# MINI_SAM_2017-01-001.net
KiCad netlist of a schematic drawn in EAGLE
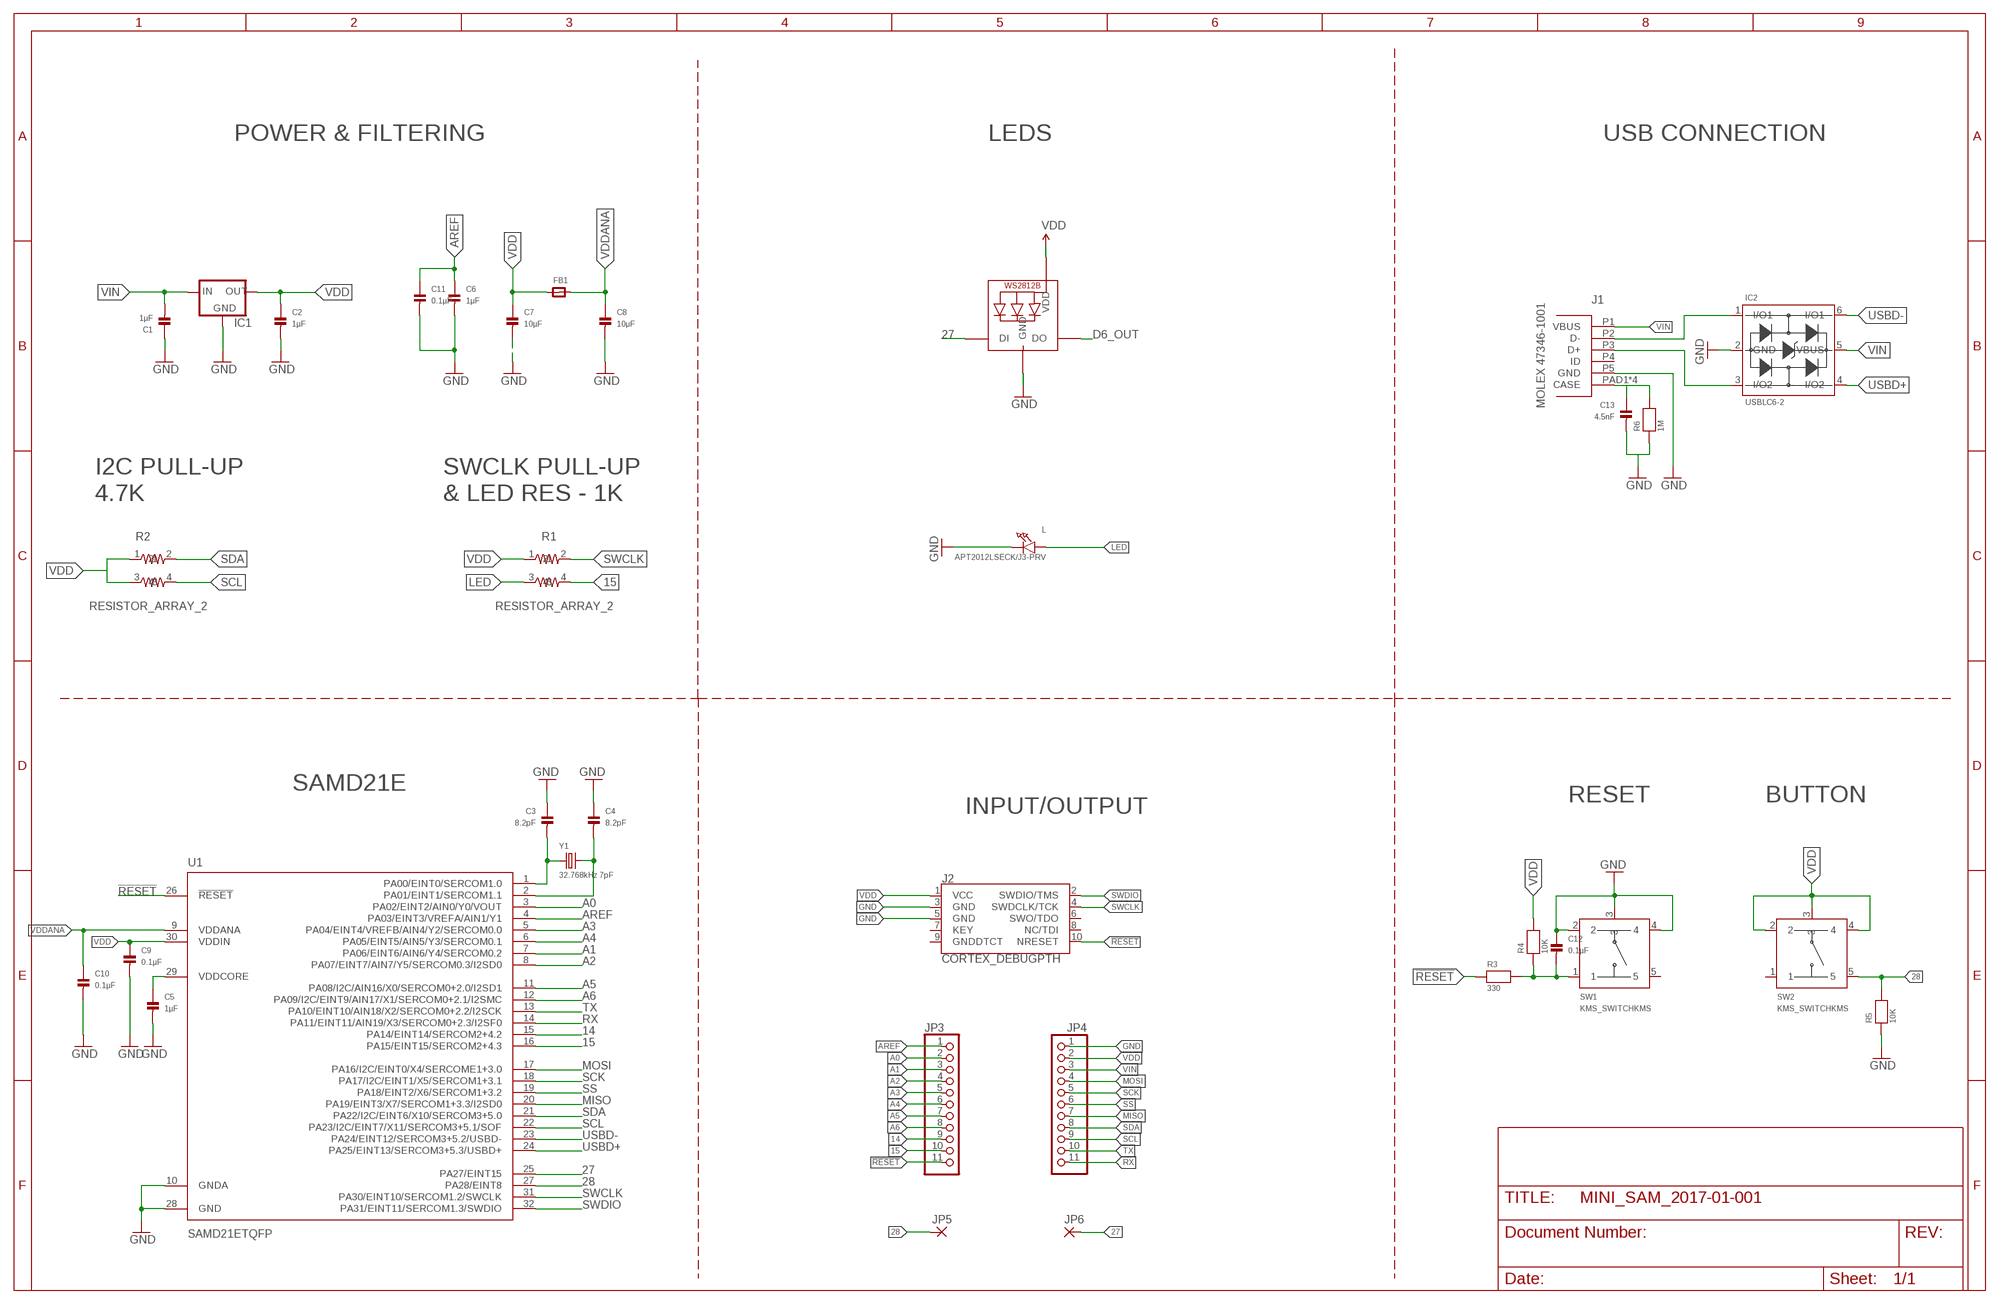
[diagram p0: schematic, sheet 1]

(export (version "E")
  (design (tool "Eeschema 10.0.6"))
  (components
    (comp (ref "C1")
      (value "1µF")
      (footprint "eagle-import:_0805MP")
      (libsource (lib "eagle-import") (part "CAP_CERAMIC_0805MP"))
    )
    (comp (ref "C2")
      (value "1µF")
      (footprint "eagle-import:_0805MP")
      (libsource (lib "eagle-import") (part "CAP_CERAMIC_0805MP"))
    )
    (comp (ref "C3")
      (value "8.2pF")
      (footprint "eagle-import:_0805MP")
      (libsource (lib "eagle-import") (part "CAP_CERAMIC_0805MP"))
    )
    (comp (ref "C4")
      (value "8.2pF")
      (footprint "eagle-import:_0805MP")
      (libsource (lib "eagle-import") (part "CAP_CERAMIC_0805MP"))
    )
    (comp (ref "C5")
      (value "1µF")
      (footprint "eagle-import:_0805MP")
      (libsource (lib "eagle-import") (part "CAP_CERAMIC_0805MP"))
    )
    (comp (ref "C6")
      (value "1µF")
      (footprint "eagle-import:_0805MP")
      (libsource (lib "eagle-import") (part "CAP_CERAMIC_0805MP"))
    )
    (comp (ref "C7")
      (value "10µF")
      (footprint "eagle-import:_0805MP")
      (libsource (lib "eagle-import") (part "CAP_CERAMIC_0805MP"))
    )
    (comp (ref "C8")
      (value "10µF")
      (footprint "eagle-import:_0805MP")
      (libsource (lib "eagle-import") (part "CAP_CERAMIC_0805MP"))
    )
    (comp (ref "C9")
      (value "0.1µF")
      (footprint "eagle-import:_0805MP")
      (libsource (lib "eagle-import") (part "CAP_CERAMIC_0805MP"))
    )
    (comp (ref "C10")
      (value "0.1µF")
      (footprint "eagle-import:_0805MP")
      (libsource (lib "eagle-import") (part "CAP_CERAMIC_0805MP"))
    )
    (comp (ref "C11")
      (value "0.1µF")
      (footprint "eagle-import:_0805MP")
      (libsource (lib "eagle-import") (part "CAP_CERAMIC_0805MP"))
    )
    (comp (ref "C12")
      (value "0.1µF")
      (footprint "eagle-import:_0805MP")
      (libsource (lib "eagle-import") (part "CAP_CERAMIC_0805MP"))
    )
    (comp (ref "C13")
      (value "4.5nF")
      (footprint "eagle-import:_0805MP")
      (libsource (lib "eagle-import") (part "CAP_CERAMIC_0805MP"))
    )
    (comp (ref "FB1")
      (value "FERRITE_0805MP")
      (footprint "eagle-import:_0805MP")
      (libsource (lib "eagle-import") (part "FERRITE_0805MP"))
    )
    (comp (ref "IC1")
      (value "MCP1700")
      (footprint "eagle-import:SOT23")
      (libsource (lib "eagle-import") (part "MCP1700"))
    )
    (comp (ref "IC2")
      (value "USBLC6-2")
      (footprint "eagle-import:SOT23-6L")
      (libsource (lib "eagle-import") (part "USBLC6-2"))
    )
    (comp (ref "J1")
      (value "MOLEX_47346-100147346")
      (footprint "eagle-import:MOLEX_47346-1001")
      (libsource (lib "eagle-import") (part "MOLEX_47346-100147346"))
    )
    (comp (ref "J2")
      (value "CORTEX_DEBUGPTH")
      (footprint "eagle-import:2X5-PTH-1.27MM")
      (libsource (lib "eagle-import") (part "CORTEX_DEBUGPTH"))
    )
    (comp (ref "JP3")
      (value "PINHD-1X111X11_SMT")
      (footprint "eagle-import:1X11_SMT")
      (libsource (lib "eagle-import") (part "PINHD-1X111X11_SMT"))
    )
    (comp (ref "JP4")
      (value "PINHD-1X111X11_SMT")
      (footprint "eagle-import:1X11_SMT")
      (libsource (lib "eagle-import") (part "PINHD-1X111X11_SMT"))
    )
    (comp (ref "JP5")
      (value "FR11_PAD2MMX1MM")
      (footprint "eagle-import:SMD2MMX1MM")
      (libsource (lib "eagle-import") (part "FR11_PAD2MMX1MM"))
    )
    (comp (ref "JP6")
      (value "FR11_PAD2MMX1MM")
      (footprint "eagle-import:SMD2MMX1MM")
      (libsource (lib "eagle-import") (part "FR11_PAD2MMX1MM"))
    )
    (comp (ref "L")
      (value "APT2012LSECK/J3-PRV")
      (footprint "eagle-import:CHIPLED_0603_NOOUTLINE")
      (libsource (lib "eagle-import") (part "LED0603_NOOUTLINE"))
    )
    (comp (ref "R1")
      (value "RESISTOR_ARRAY_2")
      (footprint "eagle-import:RESISTOR_ARRAY_0606")
      (libsource (lib "eagle-import") (part "RESISTOR_ARRAY_2"))
    )
    (comp (ref "R2")
      (value "RESISTOR_ARRAY_2")
      (footprint "eagle-import:RESISTOR_ARRAY_0606")
      (libsource (lib "eagle-import") (part "RESISTOR_ARRAY_2"))
    )
    (comp (ref "R3")
      (value "330")
      (footprint "eagle-import:_0805MP")
      (libsource (lib "eagle-import") (part "RESISTOR_0805MP"))
    )
    (comp (ref "R4")
      (value "10K")
      (footprint "eagle-import:_0805MP")
      (libsource (lib "eagle-import") (part "RESISTOR_0805MP"))
    )
    (comp (ref "R5")
      (value "10K")
      (footprint "eagle-import:_0805MP")
      (libsource (lib "eagle-import") (part "RESISTOR_0805MP"))
    )
    (comp (ref "R6")
      (value "1M")
      (footprint "eagle-import:_0805MP")
      (libsource (lib "eagle-import") (part "RESISTOR_0805MP"))
    )
    (comp (ref "STATUS")
      (value "WS2812B3535")
      (footprint "eagle-import:LED3535")
      (libsource (lib "eagle-import") (part "WS2812B3535"))
    )
    (comp (ref "SW1")
      (value "KMS_SWITCHKMS")
      (footprint "eagle-import:KMS_SWITCH")
      (libsource (lib "eagle-import") (part "KMS_SWITCHKMS"))
    )
    (comp (ref "SW2")
      (value "KMS_SWITCHKMS")
      (footprint "eagle-import:KMS_SWITCH")
      (libsource (lib "eagle-import") (part "KMS_SWITCHKMS"))
    )
    (comp (ref "U1")
      (value "SAMD21ETQFP")
      (footprint "eagle-import:TQFP32-08")
      (libsource (lib "eagle-import") (part "SAMD21ETQFP"))
    )
    (comp (ref "Y1")
      (value "32.768kHz 7pF")
      (footprint "eagle-import:_0805MP")
      (libsource (lib "eagle-import") (part "CRYSTAL0805PACKAGE"))
    )
  )
  (nets
    (net (code "1") (name "/D6_OUT") (class "Default")
      (node (ref "STATUS") (pin "3") (pinfunction "DO_3") (pintype "output"))
    )
    (net (code "2") (name "/~{RESET}") (class "Default")
      (node (ref "J2") (pin "10") (pinfunction "NRESET_10") (pintype "bidirectional"))
      (node (ref "JP3") (pin "11") (pinfunction "11_11") (pintype "passive"))
      (node (ref "R3") (pin "1") (pinfunction "1_1") (pintype "passive"))
      (node (ref "U1") (pin "26") (pinfunction "~{RESET}_26") (pintype "bidirectional"))
    )
    (net (code "3") (name "14") (class "Default")
      (node (ref "JP3") (pin "9") (pinfunction "9_9") (pintype "passive"))
      (node (ref "U1") (pin "15") (pinfunction "PA14/EINT14/SERCOM2+4.2_15") (pintype "bidirectional"))
    )
    (net (code "4") (name "15") (class "Default")
      (node (ref "JP3") (pin "10") (pinfunction "10_10") (pintype "passive"))
      (node (ref "R1") (pin "4") (pinfunction "4_4") (pintype "passive"))
      (node (ref "U1") (pin "16") (pinfunction "PA15/EINT15/SERCOM2+4.3_16") (pintype "bidirectional"))
    )
    (net (code "5") (name "27") (class "Default")
      (node (ref "JP6") (pin "P$1") (pinfunction "P_P$1") (pintype "passive"))
      (node (ref "STATUS") (pin "1") (pinfunction "DI_1") (pintype "input"))
      (node (ref "U1") (pin "25") (pinfunction "PA27/EINT15_25") (pintype "bidirectional"))
    )
    (net (code "6") (name "28") (class "Default")
      (node (ref "JP5") (pin "P$1") (pinfunction "P_P$1") (pintype "passive"))
      (node (ref "R5") (pin "2") (pinfunction "2_2") (pintype "passive"))
      (node (ref "SW2") (pin "5") (pinfunction "5_5") (pintype "bidirectional"))
      (node (ref "U1") (pin "27") (pinfunction "PA28/EINT8_27") (pintype "bidirectional"))
    )
    (net (code "7") (name "A0") (class "Default")
      (node (ref "JP3") (pin "2") (pinfunction "2_2") (pintype "passive"))
      (node (ref "U1") (pin "3") (pinfunction "PA02/EINT2/AIN0/Y0/VOUT_3") (pintype "bidirectional"))
    )
    (net (code "8") (name "A1") (class "Default")
      (node (ref "JP3") (pin "3") (pinfunction "3_3") (pintype "passive"))
      (node (ref "U1") (pin "7") (pinfunction "PA06/EINT6/AIN6/Y4/SERCOM0.2_7") (pintype "bidirectional"))
    )
    (net (code "9") (name "A2") (class "Default")
      (node (ref "JP3") (pin "4") (pinfunction "4_4") (pintype "passive"))
      (node (ref "U1") (pin "8") (pinfunction "PA07/EINT7/AIN7/Y5/SERCOM0.3/I2SD0_8") (pintype "bidirectional"))
    )
    (net (code "10") (name "A3") (class "Default")
      (node (ref "JP3") (pin "5") (pinfunction "5_5") (pintype "passive"))
      (node (ref "U1") (pin "5") (pinfunction "PA04/EINT4/VREFB/AIN4/Y2/SERCOM0.0_5") (pintype "bidirectional"))
    )
    (net (code "11") (name "A4") (class "Default")
      (node (ref "JP3") (pin "6") (pinfunction "6_6") (pintype "passive"))
      (node (ref "U1") (pin "6") (pinfunction "PA05/EINT5/AIN5/Y3/SERCOM0.1_6") (pintype "bidirectional"))
    )
    (net (code "12") (name "A5") (class "Default")
      (node (ref "JP3") (pin "7") (pinfunction "7_7") (pintype "passive"))
      (node (ref "U1") (pin "11") (pinfunction "PA08/I2C/AIN16/X0/SERCOM0+2.0/I2SD1_11") (pintype "bidirectional"))
    )
    (net (code "13") (name "A6") (class "Default")
      (node (ref "JP3") (pin "8") (pinfunction "8_8") (pintype "passive"))
      (node (ref "U1") (pin "12") (pinfunction "PA09/I2C/EINT9/AIN17/X1/SERCOM0+2.1/I2SMC_12") (pintype "bidirectional"))
    )
    (net (code "14") (name "AREF") (class "Default")
      (node (ref "C11") (pin "1") (pinfunction "P$1_1") (pintype "passive"))
      (node (ref "C6") (pin "1") (pinfunction "P$1_1") (pintype "passive"))
      (node (ref "JP3") (pin "1") (pinfunction "1_1") (pintype "passive"))
      (node (ref "U1") (pin "4") (pinfunction "PA03/EINT3/VREFA/AIN1/Y1_4") (pintype "bidirectional"))
    )
    (net (code "15") (name "GND") (class "Default")
      (node (ref "C1") (pin "1") (pinfunction "P$1_1") (pintype "passive"))
      (node (ref "C10") (pin "2") (pinfunction "P$2_2") (pintype "passive"))
      (node (ref "C11") (pin "2") (pinfunction "P$2_2") (pintype "passive"))
      (node (ref "C12") (pin "1") (pinfunction "P$1_1") (pintype "passive"))
      (node (ref "C13") (pin "2") (pinfunction "P$2_2") (pintype "passive"))
      (node (ref "C2") (pin "2") (pinfunction "P$2_2") (pintype "passive"))
      (node (ref "C3") (pin "1") (pinfunction "P$1_1") (pintype "passive"))
      (node (ref "C4") (pin "1") (pinfunction "P$1_1") (pintype "passive"))
      (node (ref "C5") (pin "2") (pinfunction "P$2_2") (pintype "passive"))
      (node (ref "C6") (pin "2") (pinfunction "P$2_2") (pintype "passive"))
      (node (ref "C7") (pin "2") (pinfunction "P$2_2") (pintype "passive"))
      (node (ref "C8") (pin "2") (pinfunction "P$2_2") (pintype "passive"))
      (node (ref "C9") (pin "2") (pinfunction "P$2_2") (pintype "passive"))
      (node (ref "IC1") (pin "1") (pinfunction "GND_1") (pintype "input"))
      (node (ref "IC2") (pin "2") (pinfunction "GND_2") (pintype "bidirectional"))
      (node (ref "J1") (pin "P5") (pinfunction "GND_P5") (pintype "power_in"))
      (node (ref "J2") (pin "3") (pinfunction "GND_3") (pintype "bidirectional"))
      (node (ref "J2") (pin "5") (pinfunction "GND_5") (pintype "bidirectional"))
      (node (ref "JP4") (pin "1") (pinfunction "1_1") (pintype "passive"))
      (node (ref "L") (pin "C") (pinfunction "C_C") (pintype "passive"))
      (node (ref "R5") (pin "1") (pinfunction "1_1") (pintype "passive"))
      (node (ref "R6") (pin "1") (pinfunction "1_1") (pintype "passive"))
      (node (ref "STATUS") (pin "4") (pinfunction "GND_4") (pintype "power_in"))
      (node (ref "SW1") (pin "2") (pinfunction "2_2") (pintype "bidirectional"))
      (node (ref "SW1") (pin "3") (pinfunction "3_3") (pintype "bidirectional"))
      (node (ref "SW1") (pin "4") (pinfunction "4_4") (pintype "bidirectional"))
      (node (ref "U1") (pin "10") (pinfunction "GNDA_10") (pintype "power_in"))
      (node (ref "U1") (pin "28") (pinfunction "GND_28") (pintype "power_in"))
    )
    (net (code "16") (name "LED") (class "Default")
      (node (ref "L") (pin "A") (pinfunction "A_A") (pintype "passive"))
      (node (ref "R1") (pin "3") (pinfunction "3_3") (pintype "passive"))
    )
    (net (code "17") (name "MISO") (class "Default")
      (node (ref "JP4") (pin "7") (pinfunction "7_7") (pintype "passive"))
      (node (ref "U1") (pin "20") (pinfunction "PA19/EINT3/X7/SERCOM1+3.3/I2SD0_20") (pintype "bidirectional"))
    )
    (net (code "18") (name "MOSI") (class "Default")
      (node (ref "JP4") (pin "4") (pinfunction "4_4") (pintype "passive"))
      (node (ref "U1") (pin "17") (pinfunction "PA16/I2C/EINT0/X4/SERCOME1+3.0_17") (pintype "bidirectional"))
    )
    (net (code "19") (name "Net-(C3-P$2)") (class "Default")
      (node (ref "C3") (pin "2") (pinfunction "P$2_2") (pintype "passive"))
      (node (ref "U1") (pin "1") (pinfunction "PA00/EINT0/SERCOM1.0_1") (pintype "bidirectional"))
      (node (ref "Y1") (pin "1") (pinfunction "1_1") (pintype "passive"))
    )
    (net (code "20") (name "Net-(C4-P$2)") (class "Default")
      (node (ref "C4") (pin "2") (pinfunction "P$2_2") (pintype "passive"))
      (node (ref "U1") (pin "2") (pinfunction "PA01/EINT1/SERCOM1.1_2") (pintype "bidirectional"))
      (node (ref "Y1") (pin "2") (pinfunction "2_2") (pintype "passive"))
    )
    (net (code "21") (name "Net-(C5-P$1)") (class "Default")
      (node (ref "C5") (pin "1") (pinfunction "P$1_1") (pintype "passive"))
      (node (ref "U1") (pin "29") (pinfunction "VDDCORE_29") (pintype "power_in"))
    )
    (net (code "22") (name "Net-(C12-P$2)") (class "Default")
      (node (ref "C12") (pin "2") (pinfunction "P$2_2") (pintype "passive"))
      (node (ref "R3") (pin "2") (pinfunction "2_2") (pintype "passive"))
      (node (ref "R4") (pin "1") (pinfunction "1_1") (pintype "passive"))
      (node (ref "SW1") (pin "1") (pinfunction "1_1") (pintype "bidirectional"))
    )
    (net (code "23") (name "Net-(C13-P$1)") (class "Default")
      (node (ref "C13") (pin "1") (pinfunction "P$1_1") (pintype "passive"))
      (node (ref "J1") (pin "PAD1") (pinfunction "CASE_PAD1") (pintype "bidirectional"))
      (node (ref "J1") (pin "PAD2") (pinfunction "CASE_PAD2") (pintype "bidirectional"))
      (node (ref "J1") (pin "PAD3") (pinfunction "CASE_PAD3") (pintype "bidirectional"))
      (node (ref "J1") (pin "PAD4") (pinfunction "CASE_PAD4") (pintype "bidirectional"))
      (node (ref "R6") (pin "2") (pinfunction "2_2") (pintype "passive"))
    )
    (net (code "24") (name "Net-(J1-D+)") (class "Default")
      (node (ref "IC2") (pin "3") (pinfunction "I/O2_3") (pintype "bidirectional"))
      (node (ref "J1") (pin "P3") (pinfunction "D+_P3") (pintype "bidirectional"))
    )
    (net (code "25") (name "Net-(J1-D-)") (class "Default")
      (node (ref "IC2") (pin "1") (pinfunction "I/O1_1") (pintype "bidirectional"))
      (node (ref "J1") (pin "P2") (pinfunction "D-_P2") (pintype "bidirectional"))
    )
    (net (code "26") (name "RX") (class "Default")
      (node (ref "JP4") (pin "11") (pinfunction "11_11") (pintype "passive"))
      (node (ref "U1") (pin "14") (pinfunction "PA11/EINT11/AIN19/X3/SERCOM0+2.3/I2SF0_14") (pintype "bidirectional"))
    )
    (net (code "27") (name "SCK") (class "Default")
      (node (ref "JP4") (pin "5") (pinfunction "5_5") (pintype "passive"))
      (node (ref "U1") (pin "18") (pinfunction "PA17/I2C/EINT1/X5/SERCOM1+3.1_18") (pintype "bidirectional"))
    )
    (net (code "28") (name "SCL") (class "Default")
      (node (ref "JP4") (pin "9") (pinfunction "9_9") (pintype "passive"))
      (node (ref "R2") (pin "4") (pinfunction "4_4") (pintype "passive"))
      (node (ref "U1") (pin "22") (pinfunction "PA23/I2C/EINT7/X11/SERCOM3+5.1/SOF_22") (pintype "bidirectional"))
    )
    (net (code "29") (name "SDA") (class "Default")
      (node (ref "JP4") (pin "8") (pinfunction "8_8") (pintype "passive"))
      (node (ref "R2") (pin "2") (pinfunction "2_2") (pintype "passive"))
      (node (ref "U1") (pin "21") (pinfunction "PA22/I2C/EINT6/X10/SERCOM3+5.0_21") (pintype "bidirectional"))
    )
    (net (code "30") (name "SS") (class "Default")
      (node (ref "JP4") (pin "6") (pinfunction "6_6") (pintype "passive"))
      (node (ref "U1") (pin "19") (pinfunction "PA18/EINT2/X6/SERCOM1+3.2_19") (pintype "bidirectional"))
    )
    (net (code "31") (name "SWCLK") (class "Default")
      (node (ref "J2") (pin "4") (pinfunction "SWDCLK/TCK_4") (pintype "bidirectional"))
      (node (ref "R1") (pin "2") (pinfunction "2_2") (pintype "passive"))
      (node (ref "U1") (pin "31") (pinfunction "PA30/EINT10/SERCOM1.2/SWCLK_31") (pintype "bidirectional"))
    )
    (net (code "32") (name "SWDIO") (class "Default")
      (node (ref "J2") (pin "2") (pinfunction "SWDIO/TMS_2") (pintype "bidirectional"))
      (node (ref "U1") (pin "32") (pinfunction "PA31/EINT11/SERCOM1.3/SWDIO_32") (pintype "bidirectional"))
    )
    (net (code "33") (name "TX") (class "Default")
      (node (ref "JP4") (pin "10") (pinfunction "10_10") (pintype "passive"))
      (node (ref "U1") (pin "13") (pinfunction "PA10/EINT10/AIN18/X2/SERCOM0+2.2/I2SCK_13") (pintype "bidirectional"))
    )
    (net (code "34") (name "USBD+") (class "Default")
      (node (ref "IC2") (pin "4") (pinfunction "I/O2_4") (pintype "bidirectional"))
      (node (ref "U1") (pin "24") (pinfunction "PA25/EINT13/SERCOM3+5.3/USBD+_24") (pintype "bidirectional"))
    )
    (net (code "35") (name "USBD-") (class "Default")
      (node (ref "IC2") (pin "6") (pinfunction "I/O1_6") (pintype "bidirectional"))
      (node (ref "U1") (pin "23") (pinfunction "PA24/EINT12/SERCOM3+5.2/USBD-_23") (pintype "bidirectional"))
    )
    (net (code "36") (name "VDD") (class "Default")
      (node (ref "C2") (pin "1") (pinfunction "P$1_1") (pintype "passive"))
      (node (ref "C7") (pin "1") (pinfunction "P$1_1") (pintype "passive"))
      (node (ref "C9") (pin "1") (pinfunction "P$1_1") (pintype "passive"))
      (node (ref "FB1") (pin "1") (pinfunction "P$1_1") (pintype "passive"))
      (node (ref "IC1") (pin "2") (pinfunction "OUT_2") (pintype "passive"))
      (node (ref "J2") (pin "1") (pinfunction "VCC_1") (pintype "bidirectional"))
      (node (ref "JP4") (pin "2") (pinfunction "2_2") (pintype "passive"))
      (node (ref "R1") (pin "1") (pinfunction "1_1") (pintype "passive"))
      (node (ref "R2") (pin "1") (pinfunction "1_1") (pintype "passive"))
      (node (ref "R2") (pin "3") (pinfunction "3_3") (pintype "passive"))
      (node (ref "R4") (pin "2") (pinfunction "2_2") (pintype "passive"))
      (node (ref "STATUS") (pin "2") (pinfunction "VDD_2") (pintype "power_in"))
      (node (ref "SW2") (pin "2") (pinfunction "2_2") (pintype "bidirectional"))
      (node (ref "SW2") (pin "3") (pinfunction "3_3") (pintype "bidirectional"))
      (node (ref "SW2") (pin "4") (pinfunction "4_4") (pintype "bidirectional"))
      (node (ref "U1") (pin "30") (pinfunction "VDDIN_30") (pintype "power_in"))
    )
    (net (code "37") (name "VDDANA") (class "Default")
      (node (ref "C10") (pin "1") (pinfunction "P$1_1") (pintype "passive"))
      (node (ref "C8") (pin "1") (pinfunction "P$1_1") (pintype "passive"))
      (node (ref "FB1") (pin "2") (pinfunction "P$2_2") (pintype "passive"))
      (node (ref "U1") (pin "9") (pinfunction "VDDANA_9") (pintype "power_in"))
    )
    (net (code "38") (name "VIN") (class "Default")
      (node (ref "C1") (pin "2") (pinfunction "P$2_2") (pintype "passive"))
      (node (ref "IC1") (pin "3") (pinfunction "IN_3") (pintype "input"))
      (node (ref "IC2") (pin "5") (pinfunction "VBUS_5") (pintype "bidirectional"))
      (node (ref "J1") (pin "P1") (pinfunction "VBUS_P1") (pintype "power_in"))
      (node (ref "JP4") (pin "3") (pinfunction "3_3") (pintype "passive"))
    )
    (net (code "39") (name "unconnected-(J1-ID-PadP4)") (class "Default")
      (node (ref "J1") (pin "P4") (pinfunction "ID_P4") (pintype "bidirectional"))
    )
    (net (code "40") (name "unconnected-(J2-GNDDTCT-Pad9)") (class "Default")
      (node (ref "J2") (pin "9") (pinfunction "GNDDTCT_9") (pintype "bidirectional"))
    )
    (net (code "41") (name "unconnected-(J2-KEY-Pad7)") (class "Default")
      (node (ref "J2") (pin "7") (pinfunction "KEY_7") (pintype "bidirectional"))
    )
    (net (code "42") (name "unconnected-(J2-NC{slash}TDI-Pad8)") (class "Default")
      (node (ref "J2") (pin "8") (pinfunction "NC/TDI_8") (pintype "bidirectional"))
    )
    (net (code "43") (name "unconnected-(J2-SWO{slash}TDO-Pad6)") (class "Default")
      (node (ref "J2") (pin "6") (pinfunction "SWO/TDO_6") (pintype "bidirectional"))
    )
    (net (code "44") (name "unconnected-(SW1-Pad5)") (class "Default")
      (node (ref "SW1") (pin "5") (pinfunction "5_5") (pintype "bidirectional"))
    )
    (net (code "45") (name "unconnected-(SW2-Pad1)") (class "Default")
      (node (ref "SW2") (pin "1") (pinfunction "1_1") (pintype "bidirectional"))
    )
  )
)
